# Bask_l__Devre_Proje_2.net
KiCad netlist of a schematic drawn in Altium Designer
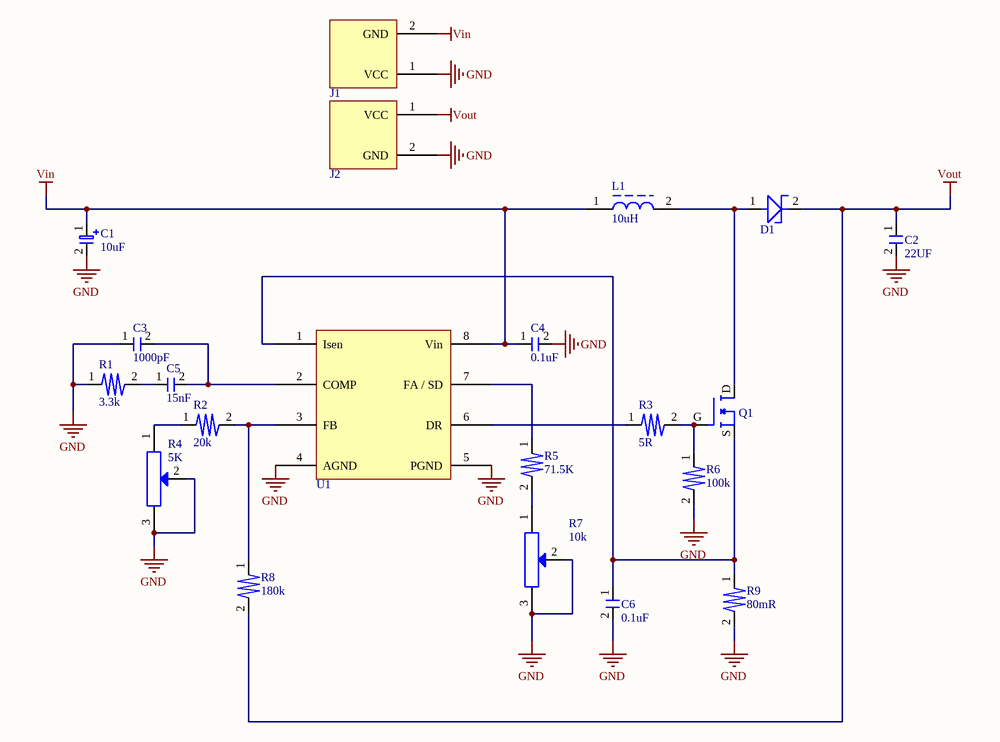
[diagram p0: Baskılı_Devre_Proje_2.SchDoc]

(export (version "E")
  (design (tool "Eeschema 10.0.6"))
  (components
    (comp (ref "C1")
      (value "10uF")
      (footprint "Radial, Can - SMD")
      (description "WCAP-ASLI Aluminum Electrolytic Capacitors")
      (fields
        (field (name "MANUFACTURER") "Wurth Electronics")
        (field (name "MANUFACTURER PART NUMBER") "865080340001")
      )
      (libsource (lib "Baskılı_Devre_Proje_2") (part "CAP ALUM 10UF 20% 16V SMD"))
    )
    (comp (ref "C2")
      (value "22UF")
      (footprint "0805 CAP SER")
      (description "Multilayer Ceramic Capacitor, 22 uF, 16 V, ± 10%, X5R, 0805 [2012 Metric]")
      (fields
        (field (name "MANUFACTURER") "Samsung")
        (field (name "MANUFACTURER PART NUMBER") "CL21A226KOQNNNG")
      )
      (libsource (lib "Baskılı_Devre_Proje_2") (part "CAP CER 22UF 16V X5R 0805"))
    )
    (comp (ref "C3")
      (value "1000pF")
      (footprint "0805 CAP SER")
      (description "Multilayer Ceramic Capacitors MLCC - SMD/SMT 16V 1000pF X7R 0805 10%")
      (fields
        (field (name "MANUFACTURER") "KEMET")
        (field (name "MANUFACTURER PART NUMBER") "C0805C102K4RACTU")
      )
      (libsource (lib "Baskılı_Devre_Proje_2") (part "CAP CER 1000PF 16V X7R 0805"))
    )
    (comp (ref "C4")
      (value "0.1uF")
      (footprint "0603 CAP SER")
      (description "100nF ±10% 16V X7R 0603 Multilayer Ceramic Capacitors MLCC - SMD/SMT RoHS")
      (fields
        (field (name "MANUFACTURER") "KEMET")
        (field (name "MANUFACTURER PART NUMBER") "C0603C104K4RACTU")
      )
      (libsource (lib "Baskılı_Devre_Proje_2") (part "CAP CER 0.1UF 16V X7R 0603"))
    )
    (comp (ref "C5")
      (value "15nF")
      (footprint "0603 CAP SER")
      (description "0.015 µF ±10% 16V Ceramic Capacitor X7R 0603 (1608 Metric)")
      (fields
        (field (name "MANUFACTURER") "KEMET")
        (field (name "MANUFACTURER PART NUMBER") "C0603C153K4RECTU")
      )
      (libsource (lib "Baskılı_Devre_Proje_2") (part "CAP CER 0603 15NF 16V X7R 10%"))
    )
    (comp (ref "C6")
      (value "0.1uF")
      (footprint "0603 CAP SER")
      (description "100nF ±10% 16V X7R 0603 Multilayer Ceramic Capacitors MLCC - SMD/SMT RoHS")
      (fields
        (field (name "MANUFACTURER") "KEMET")
        (field (name "MANUFACTURER PART NUMBER") "C0603C104K4RACTU")
      )
      (libsource (lib "Baskılı_Devre_Proje_2") (part "CAP CER 0.1UF 16V X7R 0603"))
    )
    (comp (ref "D1")
      (value "Diode 20 V 5A Surface Mount SMC")
      (footprint "DO-214AB/SMC (Diode)")
      (description "VR=20V IF=5A 300pF")
      (fields (field (name "MANUFACTURER") "Diodes") (field (name "MANUFACTURER PART NUMBER") "B520C-13-F"))
      (libsource (lib "Baskılı_Devre_Proje_2") (part "DIODE SCHOTTKY 20V 5A SMC"))
    )
    (comp (ref "J1")
      (value "TERM BLK 2POS SIDE ENT 3.5MM PCB")
      (footprint "2P 3.5MM TERMİNAL BLOCK")
      (description "Conn Terminal Block 2 POS 3.5mm Solder ST Thru-Hole 10A Box")
      (fields
        (field (name "MANUFACTURER") "Wurth Electronics")
        (field (name "MANUFACTURER PART NUMBER") "691214110002")
      )
      (libsource (lib "Baskılı_Devre_Proje_1") (part "TERM BLK 2POS SIDE ENT 3.5MM PCB"))
    )
    (comp (ref "J2")
      (value "TERM BLK 2POS SIDE ENT 3.5MM PCB")
      (footprint "2P 3.5MM TERMİNAL BLOCK")
      (description "Conn Terminal Block 2 POS 3.5mm Solder ST Thru-Hole 10A Box")
      (fields
        (field (name "MANUFACTURER") "Wurth Electronics")
        (field (name "MANUFACTURER PART NUMBER") "691214110002")
      )
      (libsource (lib "") (part "TERM BLK 2POS SIDE ENT 3.5MM PCB_1"))
    )
    (comp (ref "L1")
      (value "10uH")
      (footprint "SRN6045-100M")
      (description "Inductor Power Semi-Shielded Wirewound 10uH 20% 100KHz 17Q-Factor Ferrite 2.5A 58.6mOhm DCR T/R")
      (fields (field (name "MANUFACTURER") "Bourns") (field (name "MANUFACTURER PART NUMBER") "SRN6045-100M"))
      (libsource (lib "Baskılı_Devre_Proje_2") (part "FIXED IND 10UH 2.5A 58.6MOHM SMD"))
    )
    (comp (ref "Q1")
      (value "N-Channel 30 V 4.4A (Ta) 1.25W (Ta) Surface Mount SOT-23")
      (footprint "SOT-23")
      (description "1.25W/30V/4.4A/MOSFET/SOT-23/SINGLE N-ch")
      (fields
        (field (name "MANUFACTURER") "Pan Jit")
        (field (name "MANUFACTURER PART NUMBER") "PJA3406_R1_00001")
      )
      (libsource (lib "Baskılı_Devre_Proje_2") (part "SOT-23, MOSFET"))
    )
    (comp (ref "R1")
      (value "3.3k")
      (footprint "0805 RES")
      (description "SMD Chip Resistor, 3.3 kOhm, ï¿½ 1%, 125 mW, 0805 [2012 Metric], Thick Film, General Purpose")
      (fields
        (field (name "MANUFACTURER") "Yageo")
        (field (name "MANUFACTURER PART NUMBER") "RC0805FR-073K3L")
      )
      (libsource (lib "Baskılı_Devre_Proje_2") (part "RES 3.3K OHM 1% 1/8W 0805"))
    )
    (comp (ref "R2")
      (value "20k")
      (footprint "0805 RES")
      (description "125Mw Thick Film Resistors 100Ppm/ 1% 20K 0805 Chip Resistor Surface Mount Rohs")
      (fields
        (field (name "MANUFACTURER") "Yageo")
        (field (name "MANUFACTURER PART NUMBER") "RC0805FR-0720KL")
      )
      (libsource (lib "Baskılı_Devre_Proje_2") (part "RES 20K OHM 1% 1/8W 0805"))
    )
    (comp (ref "R3")
      (value "5R")
      (footprint "0603 RES")
      (description "Res Thin Film 0603 5 Ohm 1% 0.4W ±50ppm/C Pad SMD T/R Automotive")
      (fields
        (field (name "MANUFACTURER") "Stackpole Electronics")
        (field (name "MANUFACTURER PART NUMBER") "CSRT0603FT5R00")
      )
      (libsource (lib "Baskılı_Devre_Proje_2") (part "RES 5 OHM 1% 0.4W 0603"))
    )
    (comp (ref "R4")
      (value "5K")
      (footprint "TRİMMER")
      (description "Bourns 3296W-1-502LF 5K 10% Potentiometer Cermet Trimming 3/8\" (3296W Series)")
      (fields
        (field (name "MANUFACTURER") "Bourns")
        (field (name "MANUFACTURER PART NUMBER") "3296W-1-502LF")
      )
      (libsource (lib "Baskılı_Devre_Proje_2") (part "TRIMMER 5K OHM 0.5W PC PIN TOP"))
    )
    (comp (ref "R5")
      (value "71.5K")
      (footprint "0805 RES")
      (description "Res Thick Film 2.0 x 1.2 mm 71.5K Ohm 1% 0.125W(1/8W) 100ppm/ C Molded SMD Paper T/R")
      (fields
        (field (name "MANUFACTURER") "Yageo")
        (field (name "MANUFACTURER PART NUMBER") "RC0805FR-0771K5L")
      )
      (libsource (lib "Baskılı_Devre_Proje_2") (part "RES 71.5K OHM 1% 1/8W 0805"))
    )
    (comp (ref "R6")
      (value "100k")
      (footprint "0805 RES")
      (description "SMD Chip Resistor, 100 kOhm, ï¿½ 1%, 125 mW, 0805 [2012 Metric], Thick Film, General Purpose")
      (fields
        (field (name "MANUFACTURER") "Yageo")
        (field (name "MANUFACTURER PART NUMBER") "RC0805FR-07100KL")
      )
      (libsource (lib "Baskılı_Devre_Proje_2") (part "RES 100K OHM 1% 1/8W 0805"))
    )
    (comp (ref "R7")
      (value "10k")
      (footprint "TRİMMER")
      (description "1 kOhms .5W, 1/2W PC Pins Through Hole Trimmer Potentiometer Cermet 25. Turn Top Adjustment")
      (fields
        (field (name "MANUFACTURER") "Bourns")
        (field (name "MANUFACTURER PART NUMBER") "3296W-1-103LF")
      )
      (libsource (lib "Baskılı_Devre_Proje_2") (part "TRIMMER 10K OHM 0.5W PC PIN TOP"))
    )
    (comp (ref "R8")
      (value "180k")
      (footprint "0805 RES")
      (description "Conn Shrouded Header (4 Sides) HDR 6 POS 2.5mm Solder ST Top Entry Thru-Hole SPOX Bag")
      (fields
        (field (name "MANUFACTURER") "TE Connectivity Passive Product")
        (field (name "MANUFACTURER PART NUMBER") "CRGCQ0805F180K")
      )
      (libsource (lib "Baskılı_Devre_Proje_2") (part "RES 180K OHM 1% 1/8W 0805"))
    )
    (comp (ref "R9")
      (value "80mR")
      (footprint "0805 RES")
      (description "Low Ohmic Chip Resistor Thick Film 0805 80mOhm 5% Paper T/R")
      (fields
        (field (name "MANUFACTURER") "Yageo")
        (field (name "MANUFACTURER PART NUMBER") "RL0805JR-070R08L")
      )
      (libsource (lib "Baskılı_Devre_Proje_2") (part "RES 0.08 OHM 5% 1/8W 0805"))
    )
    (comp (ref "U1")
      (value "IC REG CTRLR MULT TOPOLOGY 8SOIC")
      (footprint "8-SOİC")
      (fields
        (field (name "MANUFACTURER") "TI National Semiconductor")
        (field (name "MANUFACTURER PART NUMBER") "LM3478MAX/NOPB")
      )
      (libsource (lib "Baskılı_Devre_Proje_2") (part "LM3478MAX/NOPB"))
    )
  )
  (nets
    (net (code "1") (name "GND") (class "Default")
      (node (ref "C1") (pin "2") (pinfunction "2_2") (pintype "passive"))
      (node (ref "C2") (pin "2") (pinfunction "2_2") (pintype "passive"))
      (node (ref "C3") (pin "1") (pinfunction "1_1") (pintype "passive"))
      (node (ref "C4") (pin "2") (pinfunction "2_2") (pintype "passive"))
      (node (ref "C6") (pin "2") (pinfunction "2_2") (pintype "passive"))
      (node (ref "J1") (pin "1") (pinfunction "VCC_1") (pintype "passive"))
      (node (ref "J2") (pin "2") (pinfunction "GND_2") (pintype "passive"))
      (node (ref "R1") (pin "1") (pinfunction "1_1") (pintype "passive"))
      (node (ref "R4") (pin "2") (pinfunction "2_2") (pintype "passive"))
      (node (ref "R4") (pin "3") (pinfunction "3_3") (pintype "passive"))
      (node (ref "R6") (pin "2") (pinfunction "2_2") (pintype "passive"))
      (node (ref "R7") (pin "2") (pinfunction "2_2") (pintype "passive"))
      (node (ref "R7") (pin "3") (pinfunction "3_3") (pintype "passive"))
      (node (ref "R9") (pin "2") (pinfunction "2_2") (pintype "passive"))
      (node (ref "U1") (pin "4") (pinfunction "AGND_4") (pintype "passive"))
      (node (ref "U1") (pin "5") (pinfunction "PGND_5") (pintype "passive"))
    )
    (net (code "2") (name "Net-(C5-Pad1)") (class "Default")
      (node (ref "C5") (pin "1") (pinfunction "1_1") (pintype "passive"))
      (node (ref "R1") (pin "2") (pinfunction "2_2") (pintype "passive"))
    )
    (net (code "3") (name "Net-(D1-Pad1)") (class "Default")
      (node (ref "D1") (pin "1") (pinfunction "1_1") (pintype "passive"))
      (node (ref "L1") (pin "2") (pinfunction "2_2") (pintype "passive"))
      (node (ref "Q1") (pin "D") (pinfunction "D_D") (pintype "passive"))
    )
    (net (code "4") (name "Net-(Q1-PadG)") (class "Default")
      (node (ref "Q1") (pin "G") (pinfunction "G_G") (pintype "passive"))
      (node (ref "R3") (pin "2") (pinfunction "2_2") (pintype "passive"))
      (node (ref "R6") (pin "1") (pinfunction "1_1") (pintype "passive"))
    )
    (net (code "5") (name "Net-(R2-Pad1)") (class "Default")
      (node (ref "R2") (pin "1") (pinfunction "1_1") (pintype "passive"))
      (node (ref "R4") (pin "1") (pinfunction "1_1") (pintype "passive"))
    )
    (net (code "6") (name "Net-(R5-Pad2)") (class "Default")
      (node (ref "R5") (pin "2") (pinfunction "2_2") (pintype "passive"))
      (node (ref "R7") (pin "1") (pinfunction "1_1") (pintype "passive"))
    )
    (net (code "7") (name "Net-(U1-COMP)") (class "Default")
      (node (ref "C3") (pin "2") (pinfunction "2_2") (pintype "passive"))
      (node (ref "C5") (pin "2") (pinfunction "2_2") (pintype "passive"))
      (node (ref "U1") (pin "2") (pinfunction "COMP_2") (pintype "passive"))
    )
    (net (code "8") (name "Net-(U1-DR)") (class "Default")
      (node (ref "R3") (pin "1") (pinfunction "1_1") (pintype "passive"))
      (node (ref "U1") (pin "6") (pinfunction "DR_6") (pintype "passive"))
    )
    (net (code "9") (name "Net-(U1-FA_{slash}_SD)") (class "Default")
      (node (ref "R5") (pin "1") (pinfunction "1_1") (pintype "passive"))
      (node (ref "U1") (pin "7") (pinfunction "FA_/_SD_7") (pintype "passive"))
    )
    (net (code "10") (name "Net-(U1-FB)") (class "Default")
      (node (ref "R2") (pin "2") (pinfunction "2_2") (pintype "passive"))
      (node (ref "R8") (pin "1") (pinfunction "1_1") (pintype "passive"))
      (node (ref "U1") (pin "3") (pinfunction "FB_3") (pintype "passive"))
    )
    (net (code "11") (name "Net-(U1-Isen)") (class "Default")
      (node (ref "C6") (pin "1") (pinfunction "1_1") (pintype "passive"))
      (node (ref "Q1") (pin "S") (pinfunction "S_S") (pintype "passive"))
      (node (ref "R9") (pin "1") (pinfunction "1_1") (pintype "passive"))
      (node (ref "U1") (pin "1") (pinfunction "Isen_1") (pintype "passive"))
    )
    (net (code "12") (name "Vin") (class "Default")
      (node (ref "C1") (pin "1") (pinfunction "1_1") (pintype "passive"))
      (node (ref "C4") (pin "1") (pinfunction "1_1") (pintype "passive"))
      (node (ref "J1") (pin "2") (pinfunction "GND_2") (pintype "passive"))
      (node (ref "L1") (pin "1") (pinfunction "1_1") (pintype "passive"))
      (node (ref "U1") (pin "8") (pinfunction "Vin_8") (pintype "passive"))
    )
    (net (code "13") (name "Vout") (class "Default")
      (node (ref "C2") (pin "1") (pinfunction "1_1") (pintype "passive"))
      (node (ref "D1") (pin "2") (pinfunction "2_2") (pintype "passive"))
      (node (ref "J2") (pin "1") (pinfunction "VCC_1") (pintype "passive"))
      (node (ref "R8") (pin "2") (pinfunction "2_2") (pintype "passive"))
    )
  )
)
